# MAX96724_COUPON.net
KiCad netlist of a schematic drawn in Altium Designer
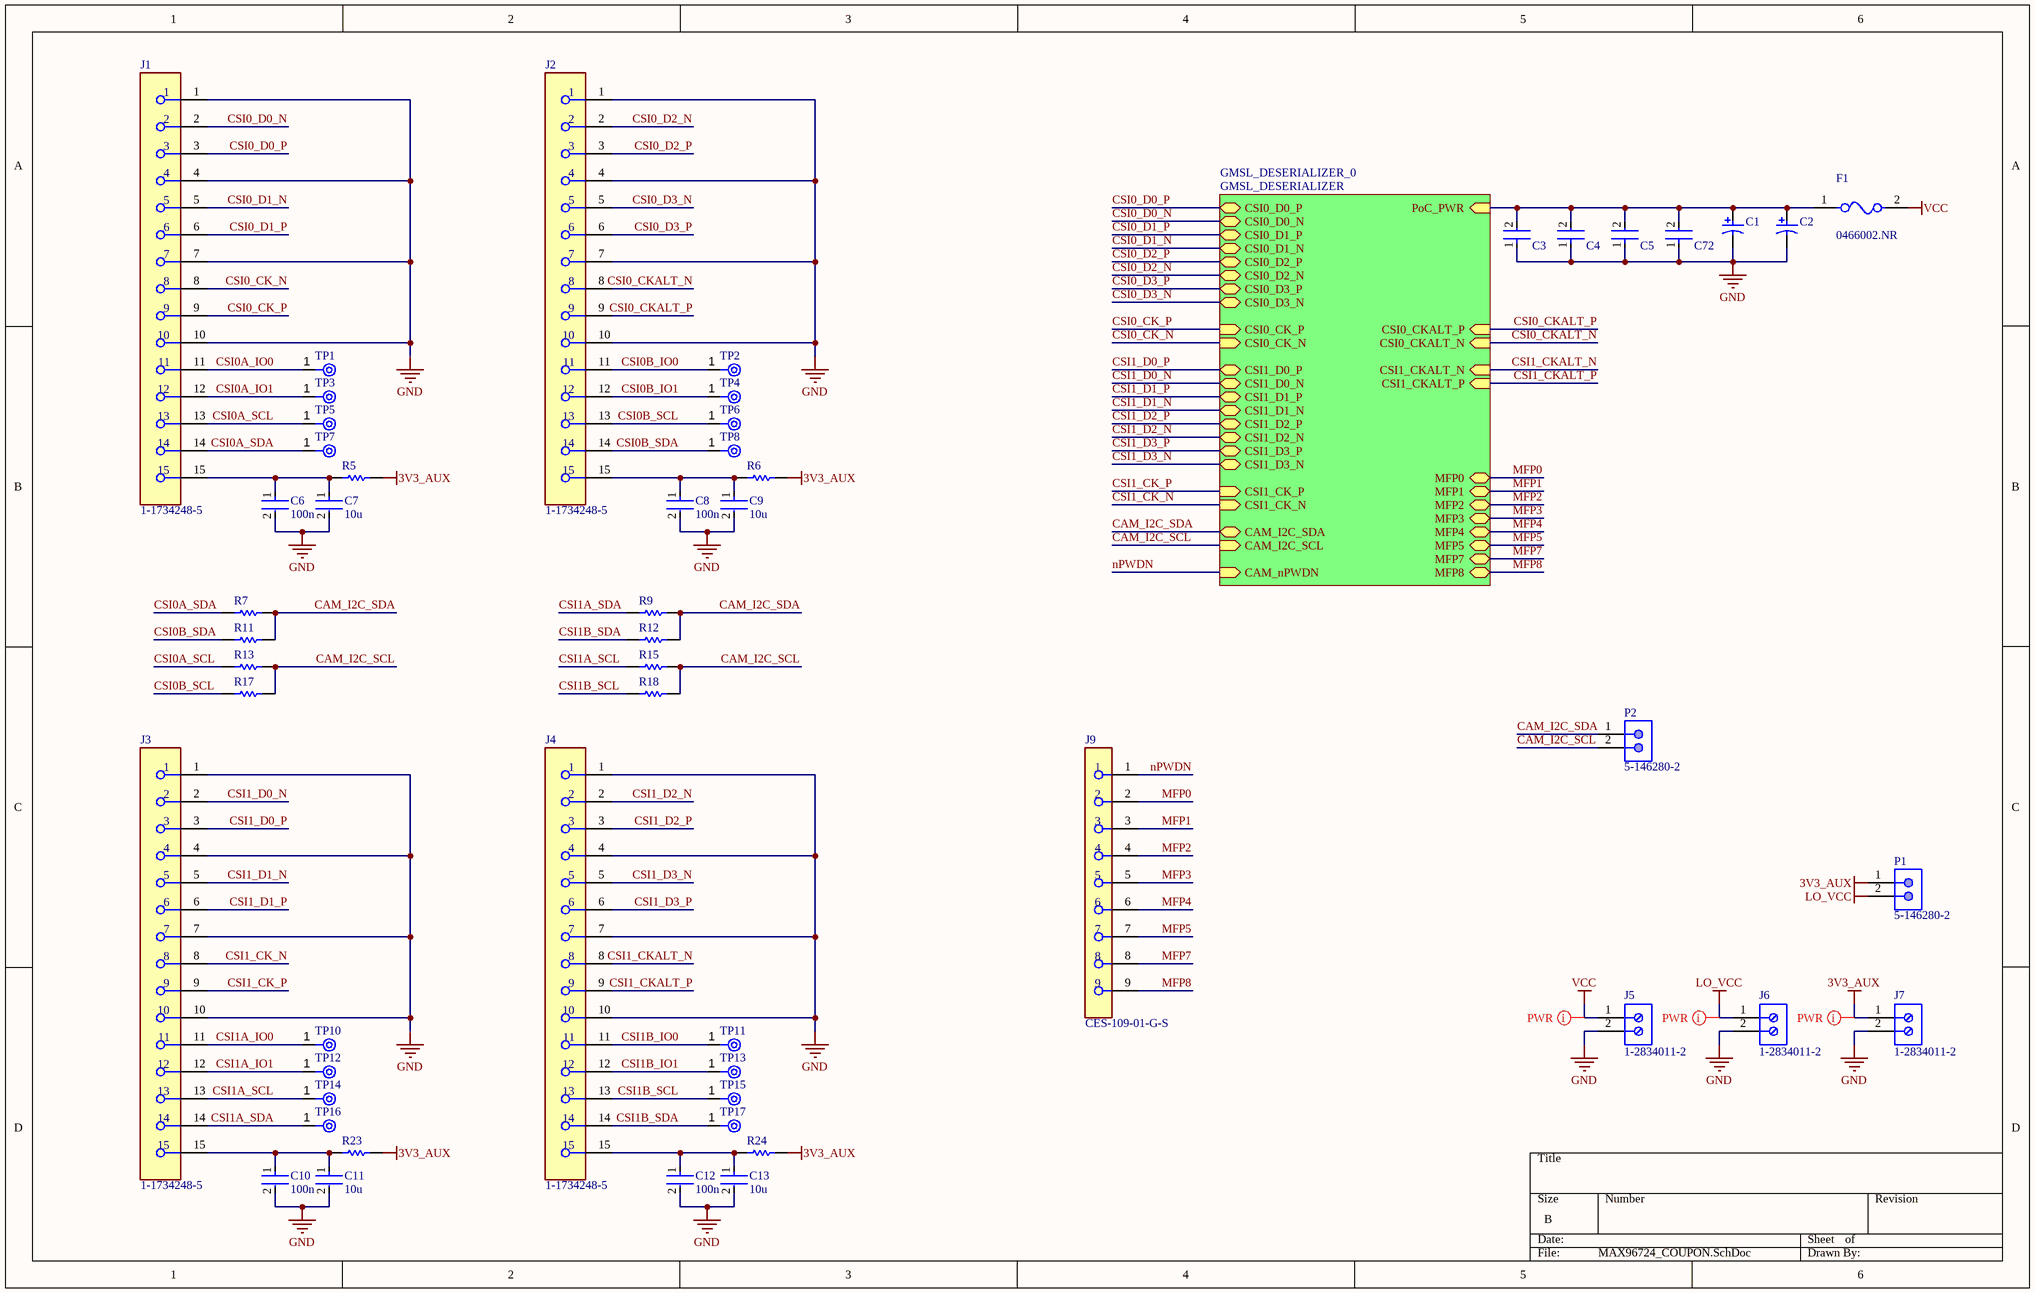
[diagram p0: MAX96724_COUPON.SchDoc]

(export (version "E")
  (design (tool "Eeschema 10.0.6"))
  (components
    (comp (ref "C1")
      (value "EEEFK1E101XP")
      (footprint "PNSC-FK-V-D8_V")
      (fields (field (name "MANUFACTURER") "Panasonic"))
      (libsource (lib "Altium Content Vault") (part "CAP-P-2"))
    )
    (comp (ref "C2")
      (value "EEEFK1E101XP")
      (footprint "PNSC-FK-V-D8_V")
      (fields (field (name "MANUFACTURER") "Panasonic"))
      (libsource (lib "Altium Content Vault") (part "CAP-P-2"))
    )
    (comp (ref "C3")
      (value "GRM21BR61E226ME44L")
      (footprint "FP-GRM21B-0_2-e0_2_0_7-IPC_B")
      (description "Chip Multilayer Ceramic Capacitors for General Purpose, 0805, 22uF, X5R, 15%, 20%, 25V")
      (fields (field (name "TOLERANCE") "20%") (field (name "VOLTAGE") "25V"))
      (libsource (lib "Altium Content Vault") (part "b4654b650e69147ec39a6b967a45e02"))
    )
    (comp (ref "C4")
      (value "GRM21BR61E226ME44L")
      (footprint "FP-GRM21B-0_2-e0_2_0_7-IPC_B")
      (description "Chip Multilayer Ceramic Capacitors for General Purpose, 0805, 22uF, X5R, 15%, 20%, 25V")
      (fields (field (name "TOLERANCE") "20%") (field (name "VOLTAGE") "25V"))
      (libsource (lib "Altium Content Vault") (part "b4654b650e69147ec39a6b967a45e02"))
    )
    (comp (ref "C5")
      (value "GRM21BR61E226ME44L")
      (footprint "FP-GRM21B-0_2-e0_2_0_7-IPC_B")
      (description "Chip Multilayer Ceramic Capacitors for General Purpose, 0805, 22uF, X5R, 15%, 20%, 25V")
      (fields (field (name "TOLERANCE") "20%") (field (name "VOLTAGE") "25V"))
      (libsource (lib "Altium Content Vault") (part "b4654b650e69147ec39a6b967a45e02"))
    )
    (comp (ref "C6")
      (value "100n")
      (footprint "FP-0402-L_1_0_0_05-W_0_5-IPC_A")
      (description "LARGE PADS, 0402 CAP, CHANGE COMMENT TO MATCH REAL P/N")
      (libsource (lib "Space Concordia") (part "b4654b650e69147ec39a6b967a45e02"))
    )
    (comp (ref "C7")
      (value "10u")
      (footprint "FP-0402-L_1_0_0_05-W_0_5-IPC_A")
      (description "LARGE PADS, 0402 CAP, CHANGE COMMENT TO MATCH REAL P/N")
      (libsource (lib "Space Concordia") (part "b4654b650e69147ec39a6b967a45e02"))
    )
    (comp (ref "C8")
      (value "100n")
      (footprint "FP-0402-L_1_0_0_05-W_0_5-IPC_A")
      (description "LARGE PADS, 0402 CAP, CHANGE COMMENT TO MATCH REAL P/N")
      (libsource (lib "Space Concordia") (part "b4654b650e69147ec39a6b967a45e02"))
    )
    (comp (ref "C9")
      (value "10u")
      (footprint "FP-0402-L_1_0_0_05-W_0_5-IPC_A")
      (description "LARGE PADS, 0402 CAP, CHANGE COMMENT TO MATCH REAL P/N")
      (libsource (lib "Space Concordia") (part "b4654b650e69147ec39a6b967a45e02"))
    )
    (comp (ref "C10")
      (value "100n")
      (footprint "FP-0402-L_1_0_0_05-W_0_5-IPC_A")
      (description "LARGE PADS, 0402 CAP, CHANGE COMMENT TO MATCH REAL P/N")
      (libsource (lib "Space Concordia") (part "b4654b650e69147ec39a6b967a45e02"))
    )
    (comp (ref "C11")
      (value "10u")
      (footprint "FP-0402-L_1_0_0_05-W_0_5-IPC_A")
      (description "LARGE PADS, 0402 CAP, CHANGE COMMENT TO MATCH REAL P/N")
      (libsource (lib "Space Concordia") (part "b4654b650e69147ec39a6b967a45e02"))
    )
    (comp (ref "C12")
      (value "100n")
      (footprint "FP-0402-L_1_0_0_05-W_0_5-IPC_A")
      (description "LARGE PADS, 0402 CAP, CHANGE COMMENT TO MATCH REAL P/N")
      (libsource (lib "Space Concordia") (part "b4654b650e69147ec39a6b967a45e02"))
    )
    (comp (ref "C13")
      (value "10u")
      (footprint "FP-0402-L_1_0_0_05-W_0_5-IPC_A")
      (description "LARGE PADS, 0402 CAP, CHANGE COMMENT TO MATCH REAL P/N")
      (libsource (lib "Space Concordia") (part "b4654b650e69147ec39a6b967a45e02"))
    )
    (comp (ref "C72")
      (value "GRM21BR61E226ME44L")
      (footprint "FP-GRM21B-0_2-e0_2_0_7-IPC_B")
      (description "Chip Multilayer Ceramic Capacitors for General Purpose, 0805, 22uF, X5R, 15%, 20%, 25V")
      (fields (field (name "TOLERANCE") "20%") (field (name "VOLTAGE") "25V"))
      (libsource (lib "Altium Content Vault") (part "b4654b650e69147ec39a6b967a45e02"))
    )
    (comp (ref "F1")
      (value "0466002.NR")
      (footprint "FP-0466-MFG")
      (description "FUSE BOARD MNT 2A 63VAC/VDC 1206")
      (fields
        (field (name "OCTOPART") "https://octopart.com/0466002.nr-littelfuse-566006")
        (field (name "MANUFACTURER") "Littelfuse")
      )
      (libsource (lib "Altium Content Vault") (part "5bcf9b9f640e542cf0359d10258e979"))
    )
    (comp (ref "J1")
      (value "1-1734248-5")
      (footprint "FP-1-1734248-5-MFG")
      (description "CONN FPC VERT 15POS 1.00MM SMD")
      (fields
        (field (name "MANUFACTURER") "TE")
        (field (name "OCTOPART") "https://octopart.com/1-1734248-5-te+connectivity-40620898")
      )
      (libsource (lib "Altium Content Vault") (part "a0777be16b290adccad2a8f9338c195"))
    )
    (comp (ref "J2")
      (value "1-1734248-5")
      (footprint "FP-1-1734248-5-MFG")
      (description "CONN FPC VERT 15POS 1.00MM SMD")
      (fields
        (field (name "MANUFACTURER") "TE")
        (field (name "OCTOPART") "https://octopart.com/1-1734248-5-te+connectivity-40620898")
      )
      (libsource (lib "Altium Content Vault") (part "a0777be16b290adccad2a8f9338c195"))
    )
    (comp (ref "J3")
      (value "1-1734248-5")
      (footprint "FP-1-1734248-5-MFG")
      (description "CONN FPC VERT 15POS 1.00MM SMD")
      (fields
        (field (name "MANUFACTURER") "TE")
        (field (name "OCTOPART") "https://octopart.com/1-1734248-5-te+connectivity-40620898")
      )
      (libsource (lib "Altium Content Vault") (part "a0777be16b290adccad2a8f9338c195"))
    )
    (comp (ref "J4")
      (value "1-1734248-5")
      (footprint "FP-1-1734248-5-MFG")
      (description "CONN FPC VERT 15POS 1.00MM SMD")
      (fields
        (field (name "MANUFACTURER") "TE")
        (field (name "OCTOPART") "https://octopart.com/1-1734248-5-te+connectivity-40620898")
      )
      (libsource (lib "Altium Content Vault") (part "a0777be16b290adccad2a8f9338c195"))
    )
    (comp (ref "J5")
      (value "1-2834011-2")
      (footprint "1-2834011-2-Footprint-1")
      (description "Barrier Strip Terminal Block")
      (libsource (lib "Space Concordia") (part "1-2834011-2"))
    )
    (comp (ref "J6")
      (value "1-2834011-2")
      (footprint "1-2834011-2-Footprint-1")
      (description "Barrier Strip Terminal Block")
      (libsource (lib "Space Concordia") (part "1-2834011-2"))
    )
    (comp (ref "J7")
      (value "1-2834011-2")
      (footprint "1-2834011-2-Footprint-1")
      (description "Barrier Strip Terminal Block")
      (libsource (lib "Space Concordia") (part "1-2834011-2"))
    )
    (comp (ref "J9")
      (value "CES-109-01-G-S")
      (footprint "FP-CES-109-01-G-S-MFG")
      (description "CES-109-01-G-S Conn Socket Strip SKT 9 POS 2.54mm Solder ST Top Entry Thru-Hole Tube")
      (libsource (lib "Altium Content Vault") (part "d3bf64047269a9dc9b641cdda8ee9d2"))
    )
    (comp (ref "P1")
      (value "5-146280-2")
      (footprint "TECO-5-146280-2_V")
      (fields (field (name "MANUFACTURER") "TE Connectivity"))
      (libsource (lib "Altium Content Vault") (part "CN-1P-M-R2"))
    )
    (comp (ref "P2")
      (value "5-146280-2")
      (footprint "TECO-5-146280-2_V")
      (fields (field (name "MANUFACTURER") "TE Connectivity"))
      (libsource (lib "Altium Content Vault") (part "CN-1P-M-R2"))
    )
    (comp (ref "R5")
      (value "RC0402JR-070RL")
      (footprint "RESC1005X40X25NL05T10")
      (fields (field (name "MANUFACTURER") "Yageo / Phycomp"))
      (libsource (lib "Altium Content Vault") (part "RES"))
    )
    (comp (ref "R6")
      (value "RC0402JR-070RL")
      (footprint "RESC1005X40X25NL05T10")
      (fields (field (name "MANUFACTURER") "Yageo / Phycomp"))
      (libsource (lib "Altium Content Vault") (part "RES"))
    )
    (comp (ref "R7")
      (value "RC0402JR-070RL")
      (footprint "RESC1005X40X25NL05T10")
      (fields (field (name "MANUFACTURER") "Yageo / Phycomp"))
      (libsource (lib "Altium Content Vault") (part "RES"))
    )
    (comp (ref "R9")
      (value "RC0402JR-070RL")
      (footprint "RESC1005X40X25NL05T10")
      (fields (field (name "MANUFACTURER") "Yageo / Phycomp"))
      (libsource (lib "Altium Content Vault") (part "RES"))
    )
    (comp (ref "R11")
      (value "RC0402JR-070RL")
      (footprint "RESC1005X40X25NL05T10")
      (fields (field (name "MANUFACTURER") "Yageo / Phycomp"))
      (libsource (lib "Altium Content Vault") (part "RES"))
    )
    (comp (ref "R12")
      (value "RC0402JR-070RL")
      (footprint "RESC1005X40X25NL05T10")
      (fields (field (name "MANUFACTURER") "Yageo / Phycomp"))
      (libsource (lib "Altium Content Vault") (part "RES"))
    )
    (comp (ref "R13")
      (value "RC0402JR-070RL")
      (footprint "RESC1005X40X25NL05T10")
      (fields (field (name "MANUFACTURER") "Yageo / Phycomp"))
      (libsource (lib "Altium Content Vault") (part "RES"))
    )
    (comp (ref "R15")
      (value "RC0402JR-070RL")
      (footprint "RESC1005X40X25NL05T10")
      (fields (field (name "MANUFACTURER") "Yageo / Phycomp"))
      (libsource (lib "Altium Content Vault") (part "RES"))
    )
    (comp (ref "R17")
      (value "RC0402JR-070RL")
      (footprint "RESC1005X40X25NL05T10")
      (fields (field (name "MANUFACTURER") "Yageo / Phycomp"))
      (libsource (lib "Altium Content Vault") (part "RES"))
    )
    (comp (ref "R18")
      (value "RC0402JR-070RL")
      (footprint "RESC1005X40X25NL05T10")
      (fields (field (name "MANUFACTURER") "Yageo / Phycomp"))
      (libsource (lib "Altium Content Vault") (part "RES"))
    )
    (comp (ref "R23")
      (value "RC0402JR-070RL")
      (footprint "RESC1005X40X25NL05T10")
      (fields (field (name "MANUFACTURER") "Yageo / Phycomp"))
      (libsource (lib "Altium Content Vault") (part "RES"))
    )
    (comp (ref "R24")
      (value "RC0402JR-070RL")
      (footprint "RESC1005X40X25NL05T10")
      (fields (field (name "MANUFACTURER") "Yageo / Phycomp"))
      (libsource (lib "Altium Content Vault") (part "RES"))
    )
    (comp (ref "TP1")
      (value "TPAD6R")
      (footprint "New footprint 1")
      (description "Test Point .6mm")
      (libsource (lib "Space Concordia") (part "TP"))
    )
    (comp (ref "TP2")
      (value "TPAD6R")
      (footprint "New footprint 1")
      (description "Test Point .6mm")
      (libsource (lib "Space Concordia") (part "TP"))
    )
    (comp (ref "TP3")
      (value "TPAD6R")
      (footprint "New footprint 1")
      (description "Test Point .6mm")
      (libsource (lib "Space Concordia") (part "TP"))
    )
    (comp (ref "TP4")
      (value "TPAD6R")
      (footprint "New footprint 1")
      (description "Test Point .6mm")
      (libsource (lib "Space Concordia") (part "TP"))
    )
    (comp (ref "TP5")
      (value "TPAD6R")
      (footprint "New footprint 1")
      (description "Test Point .6mm")
      (libsource (lib "Space Concordia") (part "TP"))
    )
    (comp (ref "TP6")
      (value "TPAD6R")
      (footprint "New footprint 1")
      (description "Test Point .6mm")
      (libsource (lib "Space Concordia") (part "TP"))
    )
    (comp (ref "TP7")
      (value "TPAD6R")
      (footprint "New footprint 1")
      (description "Test Point .6mm")
      (libsource (lib "Space Concordia") (part "TP"))
    )
    (comp (ref "TP8")
      (value "TPAD6R")
      (footprint "New footprint 1")
      (description "Test Point .6mm")
      (libsource (lib "Space Concordia") (part "TP"))
    )
    (comp (ref "TP10")
      (value "TPAD6R")
      (footprint "New footprint 1")
      (description "Test Point .6mm")
      (libsource (lib "Space Concordia") (part "TP"))
    )
    (comp (ref "TP11")
      (value "TPAD6R")
      (footprint "New footprint 1")
      (description "Test Point .6mm")
      (libsource (lib "Space Concordia") (part "TP"))
    )
    (comp (ref "TP12")
      (value "TPAD6R")
      (footprint "New footprint 1")
      (description "Test Point .6mm")
      (libsource (lib "Space Concordia") (part "TP"))
    )
    (comp (ref "TP13")
      (value "TPAD6R")
      (footprint "New footprint 1")
      (description "Test Point .6mm")
      (libsource (lib "Space Concordia") (part "TP"))
    )
    (comp (ref "TP14")
      (value "TPAD6R")
      (footprint "New footprint 1")
      (description "Test Point .6mm")
      (libsource (lib "Space Concordia") (part "TP"))
    )
    (comp (ref "TP15")
      (value "TPAD6R")
      (footprint "New footprint 1")
      (description "Test Point .6mm")
      (libsource (lib "Space Concordia") (part "TP"))
    )
    (comp (ref "TP16")
      (value "TPAD6R")
      (footprint "New footprint 1")
      (description "Test Point .6mm")
      (libsource (lib "Space Concordia") (part "TP"))
    )
    (comp (ref "TP17")
      (value "TPAD6R")
      (footprint "New footprint 1")
      (description "Test Point .6mm")
      (libsource (lib "Space Concordia") (part "TP"))
    )
  )
  (nets
    (net (code "1") (name "/CAM_I2C_SCL") (class "Default")
      (node (ref "P2") (pin "2") (pinfunction "2_2") (pintype "passive"))
      (node (ref "R13") (pin "2") (pinfunction "2_2") (pintype "passive"))
      (node (ref "R15") (pin "2") (pinfunction "2_2") (pintype "passive"))
      (node (ref "R17") (pin "2") (pinfunction "2_2") (pintype "passive"))
      (node (ref "R18") (pin "2") (pinfunction "2_2") (pintype "passive"))
    )
    (net (code "2") (name "/CAM_I2C_SDA") (class "Default")
      (node (ref "P2") (pin "1") (pinfunction "1_1") (pintype "passive"))
      (node (ref "R11") (pin "2") (pinfunction "2_2") (pintype "passive"))
      (node (ref "R12") (pin "2") (pinfunction "2_2") (pintype "passive"))
      (node (ref "R7") (pin "2") (pinfunction "2_2") (pintype "passive"))
      (node (ref "R9") (pin "2") (pinfunction "2_2") (pintype "passive"))
    )
    (net (code "3") (name "/CSI0A_IO0") (class "Default")
      (node (ref "J1") (pin "11") (pinfunction "11_11") (pintype "passive"))
      (node (ref "TP1") (pin "1") (pinfunction "TP_1") (pintype "passive"))
    )
    (net (code "4") (name "/CSI0A_IO1") (class "Default")
      (node (ref "J1") (pin "12") (pinfunction "12_12") (pintype "passive"))
      (node (ref "TP3") (pin "1") (pinfunction "TP_1") (pintype "passive"))
    )
    (net (code "5") (name "/CSI0A_SCL") (class "Default")
      (node (ref "J1") (pin "13") (pinfunction "13_13") (pintype "passive"))
      (node (ref "R13") (pin "1") (pinfunction "1_1") (pintype "passive"))
      (node (ref "TP5") (pin "1") (pinfunction "TP_1") (pintype "passive"))
    )
    (net (code "6") (name "/CSI0A_SDA") (class "Default")
      (node (ref "J1") (pin "14") (pinfunction "14_14") (pintype "passive"))
      (node (ref "R7") (pin "1") (pinfunction "1_1") (pintype "passive"))
      (node (ref "TP7") (pin "1") (pinfunction "TP_1") (pintype "passive"))
    )
    (net (code "7") (name "/CSI0B_IO0") (class "Default")
      (node (ref "J2") (pin "11") (pinfunction "11_11") (pintype "passive"))
      (node (ref "TP2") (pin "1") (pinfunction "TP_1") (pintype "passive"))
    )
    (net (code "8") (name "/CSI0B_IO1") (class "Default")
      (node (ref "J2") (pin "12") (pinfunction "12_12") (pintype "passive"))
      (node (ref "TP4") (pin "1") (pinfunction "TP_1") (pintype "passive"))
    )
    (net (code "9") (name "/CSI0B_SCL") (class "Default")
      (node (ref "J2") (pin "13") (pinfunction "13_13") (pintype "passive"))
      (node (ref "R17") (pin "1") (pinfunction "1_1") (pintype "passive"))
      (node (ref "TP6") (pin "1") (pinfunction "TP_1") (pintype "passive"))
    )
    (net (code "10") (name "/CSI0B_SDA") (class "Default")
      (node (ref "J2") (pin "14") (pinfunction "14_14") (pintype "passive"))
      (node (ref "R11") (pin "1") (pinfunction "1_1") (pintype "passive"))
      (node (ref "TP8") (pin "1") (pinfunction "TP_1") (pintype "passive"))
    )
    (net (code "11") (name "/CSI0_CKALT_N") (class "Default")
      (node (ref "J2") (pin "8") (pinfunction "8_8") (pintype "passive"))
    )
    (net (code "12") (name "/CSI0_CKALT_P") (class "Default")
      (node (ref "J2") (pin "9") (pinfunction "9_9") (pintype "passive"))
    )
    (net (code "13") (name "/CSI0_CK_N") (class "Default")
      (node (ref "J1") (pin "8") (pinfunction "8_8") (pintype "passive"))
    )
    (net (code "14") (name "/CSI0_CK_P") (class "Default")
      (node (ref "J1") (pin "9") (pinfunction "9_9") (pintype "passive"))
    )
    (net (code "15") (name "/CSI0_D0_N") (class "Default")
      (node (ref "J1") (pin "2") (pinfunction "2_2") (pintype "passive"))
    )
    (net (code "16") (name "/CSI0_D0_P") (class "Default")
      (node (ref "J1") (pin "3") (pinfunction "3_3") (pintype "passive"))
    )
    (net (code "17") (name "/CSI0_D1_N") (class "Default")
      (node (ref "J1") (pin "5") (pinfunction "5_5") (pintype "passive"))
    )
    (net (code "18") (name "/CSI0_D1_P") (class "Default")
      (node (ref "J1") (pin "6") (pinfunction "6_6") (pintype "passive"))
    )
    (net (code "19") (name "/CSI0_D2_N") (class "Default")
      (node (ref "J2") (pin "2") (pinfunction "2_2") (pintype "passive"))
    )
    (net (code "20") (name "/CSI0_D2_P") (class "Default")
      (node (ref "J2") (pin "3") (pinfunction "3_3") (pintype "passive"))
    )
    (net (code "21") (name "/CSI0_D3_N") (class "Default")
      (node (ref "J2") (pin "5") (pinfunction "5_5") (pintype "passive"))
    )
    (net (code "22") (name "/CSI0_D3_P") (class "Default")
      (node (ref "J2") (pin "6") (pinfunction "6_6") (pintype "passive"))
    )
    (net (code "23") (name "/CSI1A_IO0") (class "Default")
      (node (ref "J3") (pin "11") (pinfunction "11_11") (pintype "passive"))
      (node (ref "TP10") (pin "1") (pinfunction "TP_1") (pintype "passive"))
    )
    (net (code "24") (name "/CSI1A_IO1") (class "Default")
      (node (ref "J3") (pin "12") (pinfunction "12_12") (pintype "passive"))
      (node (ref "TP12") (pin "1") (pinfunction "TP_1") (pintype "passive"))
    )
    (net (code "25") (name "/CSI1A_SCL") (class "Default")
      (node (ref "J3") (pin "13") (pinfunction "13_13") (pintype "passive"))
      (node (ref "R15") (pin "1") (pinfunction "1_1") (pintype "passive"))
      (node (ref "TP14") (pin "1") (pinfunction "TP_1") (pintype "passive"))
    )
    (net (code "26") (name "/CSI1A_SDA") (class "Default")
      (node (ref "J3") (pin "14") (pinfunction "14_14") (pintype "passive"))
      (node (ref "R9") (pin "1") (pinfunction "1_1") (pintype "passive"))
      (node (ref "TP16") (pin "1") (pinfunction "TP_1") (pintype "passive"))
    )
    (net (code "27") (name "/CSI1B_IO0") (class "Default")
      (node (ref "J4") (pin "11") (pinfunction "11_11") (pintype "passive"))
      (node (ref "TP11") (pin "1") (pinfunction "TP_1") (pintype "passive"))
    )
    (net (code "28") (name "/CSI1B_IO1") (class "Default")
      (node (ref "J4") (pin "12") (pinfunction "12_12") (pintype "passive"))
      (node (ref "TP13") (pin "1") (pinfunction "TP_1") (pintype "passive"))
    )
    (net (code "29") (name "/CSI1B_SCL") (class "Default")
      (node (ref "J4") (pin "13") (pinfunction "13_13") (pintype "passive"))
      (node (ref "R18") (pin "1") (pinfunction "1_1") (pintype "passive"))
      (node (ref "TP15") (pin "1") (pinfunction "TP_1") (pintype "passive"))
    )
    (net (code "30") (name "/CSI1B_SDA") (class "Default")
      (node (ref "J4") (pin "14") (pinfunction "14_14") (pintype "passive"))
      (node (ref "R12") (pin "1") (pinfunction "1_1") (pintype "passive"))
      (node (ref "TP17") (pin "1") (pinfunction "TP_1") (pintype "passive"))
    )
    (net (code "31") (name "/CSI1_CKALT_N") (class "Default")
      (node (ref "J4") (pin "8") (pinfunction "8_8") (pintype "passive"))
    )
    (net (code "32") (name "/CSI1_CKALT_P") (class "Default")
      (node (ref "J4") (pin "9") (pinfunction "9_9") (pintype "passive"))
    )
    (net (code "33") (name "/CSI1_CK_N") (class "Default")
      (node (ref "J3") (pin "8") (pinfunction "8_8") (pintype "passive"))
    )
    (net (code "34") (name "/CSI1_CK_P") (class "Default")
      (node (ref "J3") (pin "9") (pinfunction "9_9") (pintype "passive"))
    )
    (net (code "35") (name "/CSI1_D0_N") (class "Default")
      (node (ref "J3") (pin "2") (pinfunction "2_2") (pintype "passive"))
    )
    (net (code "36") (name "/CSI1_D0_P") (class "Default")
      (node (ref "J3") (pin "3") (pinfunction "3_3") (pintype "passive"))
    )
    (net (code "37") (name "/CSI1_D1_N") (class "Default")
      (node (ref "J3") (pin "5") (pinfunction "5_5") (pintype "passive"))
    )
    (net (code "38") (name "/CSI1_D1_P") (class "Default")
      (node (ref "J3") (pin "6") (pinfunction "6_6") (pintype "passive"))
    )
    (net (code "39") (name "/CSI1_D2_N") (class "Default")
      (node (ref "J4") (pin "2") (pinfunction "2_2") (pintype "passive"))
    )
    (net (code "40") (name "/CSI1_D2_P") (class "Default")
      (node (ref "J4") (pin "3") (pinfunction "3_3") (pintype "passive"))
    )
    (net (code "41") (name "/CSI1_D3_N") (class "Default")
      (node (ref "J4") (pin "5") (pinfunction "5_5") (pintype "passive"))
    )
    (net (code "42") (name "/CSI1_D3_P") (class "Default")
      (node (ref "J4") (pin "6") (pinfunction "6_6") (pintype "passive"))
    )
    (net (code "43") (name "/MFP0") (class "Default")
      (node (ref "J9") (pin "2") (pinfunction "2_2") (pintype "passive"))
    )
    (net (code "44") (name "/MFP1") (class "Default")
      (node (ref "J9") (pin "3") (pinfunction "3_3") (pintype "passive"))
    )
    (net (code "45") (name "/MFP2") (class "Default")
      (node (ref "J9") (pin "4") (pinfunction "4_4") (pintype "passive"))
    )
    (net (code "46") (name "/MFP3") (class "Default")
      (node (ref "J9") (pin "5") (pinfunction "5_5") (pintype "passive"))
    )
    (net (code "47") (name "/MFP4") (class "Default")
      (node (ref "J9") (pin "6") (pinfunction "6_6") (pintype "passive"))
    )
    (net (code "48") (name "/MFP5") (class "Default")
      (node (ref "J9") (pin "7") (pinfunction "7_7") (pintype "passive"))
    )
    (net (code "49") (name "/MFP7") (class "Default")
      (node (ref "J9") (pin "8") (pinfunction "8_8") (pintype "passive"))
    )
    (net (code "50") (name "/MFP8") (class "Default")
      (node (ref "J9") (pin "9") (pinfunction "9_9") (pintype "passive"))
    )
    (net (code "51") (name "/PoC_PWR") (class "Default")
      (node (ref "C1") (pin "1") (pinfunction "1_1") (pintype "passive"))
      (node (ref "C2") (pin "1") (pinfunction "1_1") (pintype "passive"))
      (node (ref "C3") (pin "2") (pinfunction "2_2") (pintype "passive"))
      (node (ref "C4") (pin "2") (pinfunction "2_2") (pintype "passive"))
      (node (ref "C5") (pin "2") (pinfunction "2_2") (pintype "passive"))
      (node (ref "C72") (pin "2") (pinfunction "2_2") (pintype "passive"))
      (node (ref "F1") (pin "1") (pinfunction "1_1") (pintype "passive"))
    )
    (net (code "52") (name "/nPWDN") (class "Default")
      (node (ref "J9") (pin "1") (pinfunction "1_1") (pintype "passive"))
    )
    (net (code "53") (name "3V3_AUX") (class "Default")
      (node (ref "J7") (pin "1") (pinfunction "1_1") (pintype "passive"))
      (node (ref "P1") (pin "1") (pinfunction "1_1") (pintype "passive"))
      (node (ref "R23") (pin "2") (pinfunction "2_2") (pintype "passive"))
      (node (ref "R24") (pin "2") (pinfunction "2_2") (pintype "passive"))
      (node (ref "R5") (pin "2") (pinfunction "2_2") (pintype "passive"))
      (node (ref "R6") (pin "2") (pinfunction "2_2") (pintype "passive"))
    )
    (net (code "54") (name "GND") (class "Default")
      (node (ref "C1") (pin "2") (pinfunction "2_2") (pintype "passive"))
      (node (ref "C10") (pin "2") (pinfunction "2_2") (pintype "passive"))
      (node (ref "C11") (pin "2") (pinfunction "2_2") (pintype "passive"))
      (node (ref "C12") (pin "2") (pinfunction "2_2") (pintype "passive"))
      (node (ref "C13") (pin "2") (pinfunction "2_2") (pintype "passive"))
      (node (ref "C2") (pin "2") (pinfunction "2_2") (pintype "passive"))
      (node (ref "C3") (pin "1") (pinfunction "1_1") (pintype "passive"))
      (node (ref "C4") (pin "1") (pinfunction "1_1") (pintype "passive"))
      (node (ref "C5") (pin "1") (pinfunction "1_1") (pintype "passive"))
      (node (ref "C6") (pin "2") (pinfunction "2_2") (pintype "passive"))
      (node (ref "C7") (pin "2") (pinfunction "2_2") (pintype "passive"))
      (node (ref "C72") (pin "1") (pinfunction "1_1") (pintype "passive"))
      (node (ref "C8") (pin "2") (pinfunction "2_2") (pintype "passive"))
      (node (ref "C9") (pin "2") (pinfunction "2_2") (pintype "passive"))
      (node (ref "J1") (pin "1") (pinfunction "1_1") (pintype "passive"))
      (node (ref "J1") (pin "10") (pinfunction "10_10") (pintype "passive"))
      (node (ref "J1") (pin "4") (pinfunction "4_4") (pintype "passive"))
      (node (ref "J1") (pin "7") (pinfunction "7_7") (pintype "passive"))
      (node (ref "J2") (pin "1") (pinfunction "1_1") (pintype "passive"))
      (node (ref "J2") (pin "10") (pinfunction "10_10") (pintype "passive"))
      (node (ref "J2") (pin "4") (pinfunction "4_4") (pintype "passive"))
      (node (ref "J2") (pin "7") (pinfunction "7_7") (pintype "passive"))
      (node (ref "J3") (pin "1") (pinfunction "1_1") (pintype "passive"))
      (node (ref "J3") (pin "10") (pinfunction "10_10") (pintype "passive"))
      (node (ref "J3") (pin "4") (pinfunction "4_4") (pintype "passive"))
      (node (ref "J3") (pin "7") (pinfunction "7_7") (pintype "passive"))
      (node (ref "J4") (pin "1") (pinfunction "1_1") (pintype "passive"))
      (node (ref "J4") (pin "10") (pinfunction "10_10") (pintype "passive"))
      (node (ref "J4") (pin "4") (pinfunction "4_4") (pintype "passive"))
      (node (ref "J4") (pin "7") (pinfunction "7_7") (pintype "passive"))
      (node (ref "J5") (pin "2") (pinfunction "2_2") (pintype "passive"))
      (node (ref "J6") (pin "2") (pinfunction "2_2") (pintype "passive"))
      (node (ref "J7") (pin "2") (pinfunction "2_2") (pintype "passive"))
    )
    (net (code "55") (name "LO_VCC") (class "Default")
      (node (ref "J6") (pin "1") (pinfunction "1_1") (pintype "passive"))
      (node (ref "P1") (pin "2") (pinfunction "2_2") (pintype "passive"))
    )
    (net (code "56") (name "Net-(C6-Pad1)") (class "Default")
      (node (ref "C6") (pin "1") (pinfunction "1_1") (pintype "passive"))
      (node (ref "C7") (pin "1") (pinfunction "1_1") (pintype "passive"))
      (node (ref "J1") (pin "15") (pinfunction "15_15") (pintype "passive"))
      (node (ref "R5") (pin "1") (pinfunction "1_1") (pintype "passive"))
    )
    (net (code "57") (name "Net-(C8-Pad1)") (class "Default")
      (node (ref "C8") (pin "1") (pinfunction "1_1") (pintype "passive"))
      (node (ref "C9") (pin "1") (pinfunction "1_1") (pintype "passive"))
      (node (ref "J2") (pin "15") (pinfunction "15_15") (pintype "passive"))
      (node (ref "R6") (pin "1") (pinfunction "1_1") (pintype "passive"))
    )
    (net (code "58") (name "Net-(C10-Pad1)") (class "Default")
      (node (ref "C10") (pin "1") (pinfunction "1_1") (pintype "passive"))
      (node (ref "C11") (pin "1") (pinfunction "1_1") (pintype "passive"))
      (node (ref "J3") (pin "15") (pinfunction "15_15") (pintype "passive"))
      (node (ref "R23") (pin "1") (pinfunction "1_1") (pintype "passive"))
    )
    (net (code "59") (name "Net-(C12-Pad1)") (class "Default")
      (node (ref "C12") (pin "1") (pinfunction "1_1") (pintype "passive"))
      (node (ref "C13") (pin "1") (pinfunction "1_1") (pintype "passive"))
      (node (ref "J4") (pin "15") (pinfunction "15_15") (pintype "passive"))
      (node (ref "R24") (pin "1") (pinfunction "1_1") (pintype "passive"))
    )
    (net (code "60") (name "VCC") (class "Default")
      (node (ref "F1") (pin "2") (pinfunction "2_2") (pintype "passive"))
      (node (ref "J5") (pin "1") (pinfunction "1_1") (pintype "passive"))
    )
  )
)
